# Sensorboard.net
KiCad netlist of a schematic drawn in EAGLE
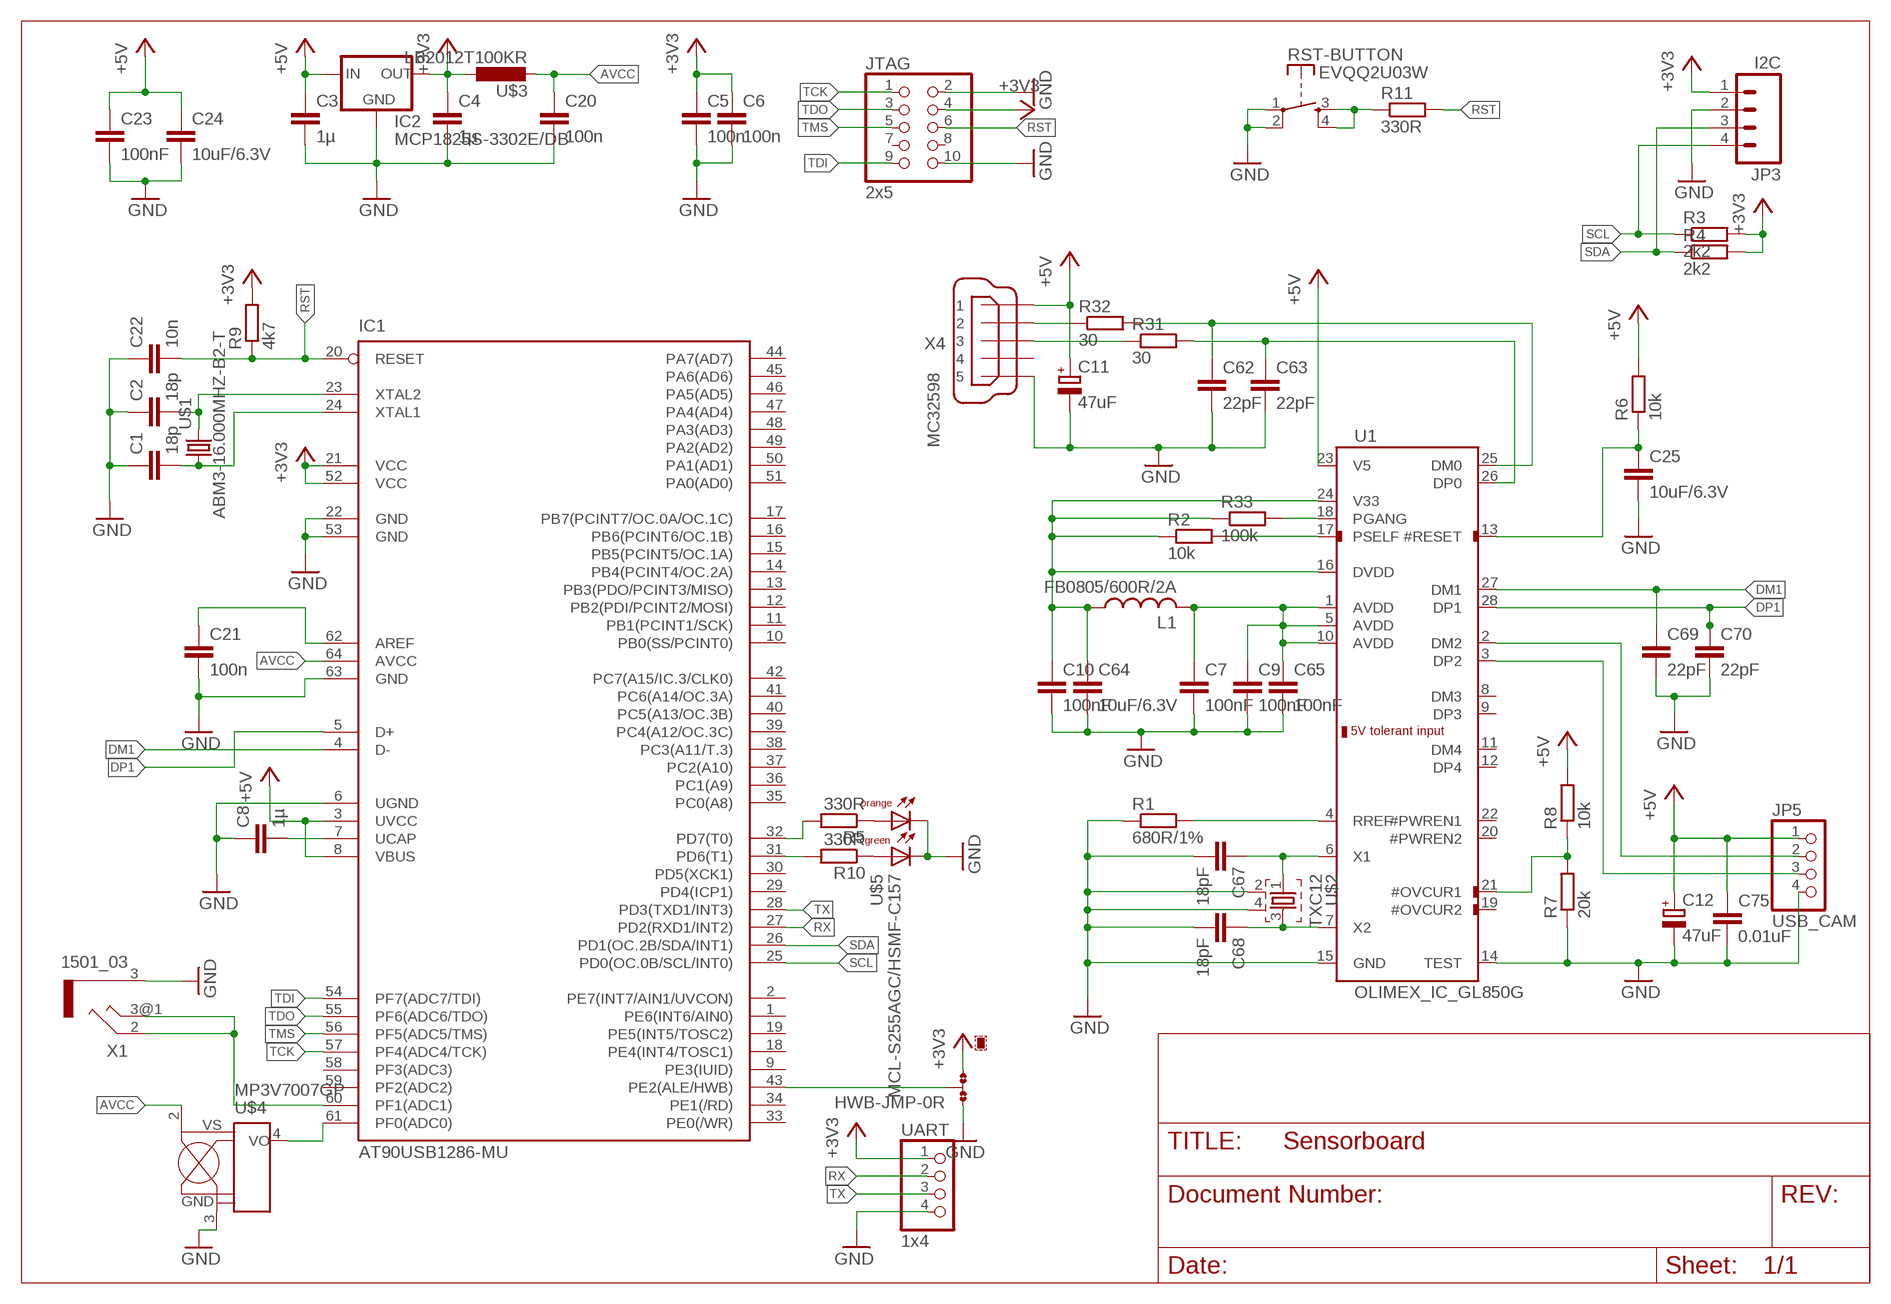
[diagram p0: schematic, sheet 1]

(export (version "E")
  (design (tool "Eeschema 10.0.6"))
  (components
    (comp (ref "C1")
      (value "18p")
      (footprint "eagle-import:C0603K")
      (libsource (lib "eagle-import") (part "C-EUC0603K"))
    )
    (comp (ref "C2")
      (value "18p")
      (footprint "eagle-import:C0603K")
      (libsource (lib "eagle-import") (part "C-EUC0603K"))
    )
    (comp (ref "C3")
      (value "1µ")
      (footprint "eagle-import:C0603K")
      (libsource (lib "eagle-import") (part "C-EUC0603K"))
    )
    (comp (ref "C4")
      (value "1µ")
      (footprint "eagle-import:C0603K")
      (libsource (lib "eagle-import") (part "C-EUC0603K"))
    )
    (comp (ref "C5")
      (value "100n")
      (footprint "eagle-import:C0603K")
      (libsource (lib "eagle-import") (part "C-EUC0603K"))
    )
    (comp (ref "C6")
      (value "100n")
      (footprint "eagle-import:C0603K")
      (libsource (lib "eagle-import") (part "C-EUC0603K"))
    )
    (comp (ref "C7")
      (value "100nF")
      (footprint "eagle-import:C0603")
      (libsource (lib "eagle-import") (part "C-EUC0603"))
    )
    (comp (ref "C8")
      (value "1µ")
      (footprint "eagle-import:C0603K")
      (libsource (lib "eagle-import") (part "C-EUC0603K"))
    )
    (comp (ref "C9")
      (value "100nF")
      (footprint "eagle-import:C0603")
      (libsource (lib "eagle-import") (part "C-EUC0603"))
    )
    (comp (ref "C10")
      (value "100nF")
      (footprint "eagle-import:C0603")
      (libsource (lib "eagle-import") (part "C-EUC0603"))
    )
    (comp (ref "C11")
      (value "47uF")
      (footprint "eagle-import:SMC_E")
      (libsource (lib "eagle-import") (part "CPOL-EUSMCE"))
    )
    (comp (ref "C12")
      (value "47uF")
      (footprint "eagle-import:SMC_E")
      (libsource (lib "eagle-import") (part "CPOL-EUSMCE"))
    )
    (comp (ref "C20")
      (value "100n")
      (footprint "eagle-import:C0603K")
      (libsource (lib "eagle-import") (part "C-EUC0603K"))
    )
    (comp (ref "C21")
      (value "100n")
      (footprint "eagle-import:C0603K")
      (libsource (lib "eagle-import") (part "C-EUC0603K"))
    )
    (comp (ref "C22")
      (value "10n")
      (footprint "eagle-import:C0603K")
      (libsource (lib "eagle-import") (part "C-EUC0603K"))
    )
    (comp (ref "C23")
      (value "100nF")
      (footprint "eagle-import:C0603")
      (libsource (lib "eagle-import") (part "C-EUC0603"))
    )
    (comp (ref "C24")
      (value "10uF/6.3V")
      (footprint "eagle-import:C0805")
      (libsource (lib "eagle-import") (part "C-EUC0805"))
    )
    (comp (ref "C25")
      (value "10uF/6.3V")
      (footprint "eagle-import:C0805")
      (libsource (lib "eagle-import") (part "C-EUC0805"))
    )
    (comp (ref "C62")
      (value "22pF")
      (footprint "eagle-import:C0603")
      (libsource (lib "eagle-import") (part "C-EUC0603"))
    )
    (comp (ref "C63")
      (value "22pF")
      (footprint "eagle-import:C0603")
      (libsource (lib "eagle-import") (part "C-EUC0603"))
    )
    (comp (ref "C64")
      (value "10uF/6.3V")
      (footprint "eagle-import:C0805")
      (libsource (lib "eagle-import") (part "C-EUC0805"))
    )
    (comp (ref "C65")
      (value "100nF")
      (footprint "eagle-import:C0603")
      (libsource (lib "eagle-import") (part "C-EUC0603"))
    )
    (comp (ref "C67")
      (value "18pF")
      (footprint "eagle-import:C0603")
      (libsource (lib "eagle-import") (part "C-EUC0603"))
    )
    (comp (ref "C68")
      (value "18pF")
      (footprint "eagle-import:C0603")
      (libsource (lib "eagle-import") (part "C-EUC0603"))
    )
    (comp (ref "C69")
      (value "22pF")
      (footprint "eagle-import:C0603")
      (libsource (lib "eagle-import") (part "C-EUC0603"))
    )
    (comp (ref "C70")
      (value "22pF")
      (footprint "eagle-import:C0603")
      (libsource (lib "eagle-import") (part "C-EUC0603"))
    )
    (comp (ref "C75")
      (value "0.01uF")
      (footprint "eagle-import:C0603")
      (libsource (lib "eagle-import") (part "C-EUC0603"))
    )
    (comp (ref "HWB-JMP")
      (value "0R-JUMPB")
      (footprint "eagle-import:B0R-JMP")
      (libsource (lib "eagle-import") (part "0R-JUMPB"))
    )
    (comp (ref "IC1")
      (value "AT90USB1286-MU")
      (footprint "eagle-import:TQFP64")
      (libsource (lib "eagle-import") (part "AT90USB1287-AU"))
    )
    (comp (ref "IC2")
      (value "MCP1825S-3302E/DB")
      (footprint "eagle-import:SOT223")
      (libsource (lib "eagle-import") (part "MCP1825-SOT223"))
    )
    (comp (ref "JP3")
      (value "I2C")
      (footprint "eagle-import:1X04")
      (libsource (lib "eagle-import") (part "M04PTH"))
    )
    (comp (ref "JP5")
      (value "USB_CAM")
      (footprint "eagle-import:1X04")
      (libsource (lib "eagle-import") (part "PINHD-1X4"))
    )
    (comp (ref "JTAG")
      (value "2x5")
      (footprint "eagle-import:2X05")
      (libsource (lib "eagle-import") (part "PINHD-2X5"))
    )
    (comp (ref "L1")
      (value "FB0805/600R/2A")
      (footprint "eagle-import:L3225P")
      (libsource (lib "eagle-import") (part "L-USL3225P"))
    )
    (comp (ref "R1")
      (value "680R/1%")
      (footprint "eagle-import:R0603")
      (libsource (lib "eagle-import") (part "R-EU_R0603"))
    )
    (comp (ref "R2")
      (value "10k")
      (footprint "eagle-import:R0603")
      (libsource (lib "eagle-import") (part "R-EU_R0603"))
    )
    (comp (ref "R3")
      (value "2k2")
      (footprint "eagle-import:R0603")
      (libsource (lib "eagle-import") (part "R-EU_R0603"))
    )
    (comp (ref "R4")
      (value "2k2")
      (footprint "eagle-import:R0603")
      (libsource (lib "eagle-import") (part "R-EU_R0603"))
    )
    (comp (ref "R5")
      (value "330R")
      (footprint "eagle-import:R0603")
      (libsource (lib "eagle-import") (part "R-EU_R0603"))
    )
    (comp (ref "R6")
      (value "10k")
      (footprint "eagle-import:R0603")
      (libsource (lib "eagle-import") (part "R-EU_R0603"))
    )
    (comp (ref "R7")
      (value "20k")
      (footprint "eagle-import:R0603")
      (libsource (lib "eagle-import") (part "R-EU_R0603"))
    )
    (comp (ref "R8")
      (value "10k")
      (footprint "eagle-import:R0603")
      (libsource (lib "eagle-import") (part "R-EU_R0603"))
    )
    (comp (ref "R9")
      (value "4k7")
      (footprint "eagle-import:R0603")
      (libsource (lib "eagle-import") (part "R-EU_R0603"))
    )
    (comp (ref "R10")
      (value "330R")
      (footprint "eagle-import:R0603")
      (libsource (lib "eagle-import") (part "R-EU_R0603"))
    )
    (comp (ref "R11")
      (value "330R")
      (footprint "eagle-import:R0603")
      (libsource (lib "eagle-import") (part "R-EU_R0603"))
    )
    (comp (ref "R31")
      (value "30")
      (footprint "eagle-import:R0603")
      (libsource (lib "eagle-import") (part "R-EU_R0603"))
    )
    (comp (ref "R32")
      (value "30")
      (footprint "eagle-import:R0603")
      (libsource (lib "eagle-import") (part "R-EU_R0603"))
    )
    (comp (ref "R33")
      (value "100k")
      (footprint "eagle-import:R0603")
      (libsource (lib "eagle-import") (part "R-EU_R0603"))
    )
    (comp (ref "RST-BUTTON")
      (value "EVQQ2U03W")
      (footprint "eagle-import:EVQQ2")
      (libsource (lib "eagle-import") (part "SWITCH-SPNO"))
    )
    (comp (ref "U$1")
      (value "ABM3-16.000MHZ-B2-T")
      (footprint "eagle-import:SMD_5X3.2MM")
      (libsource (lib "eagle-import") (part "TXC_ABM3"))
    )
    (comp (ref "U$2")
      (value "TXC12")
      (footprint "eagle-import:CTS406")
      (libsource (lib "eagle-import") (part "TXC12"))
    )
    (comp (ref "U$3")
      (value "LB2012T100KR")
      (footprint "eagle-import:L-2012")
      (libsource (lib "eagle-import") (part "L-TAIYO-YUDEN"))
    )
    (comp (ref "U$4")
      (value "MP3V7007GP")
      (footprint "eagle-import:SOP-8")
      (libsource (lib "eagle-import") (part "MP3V7007GP"))
    )
    (comp (ref "U$5")
      (value "MCL-S255AGC/HSMF-C157")
      (footprint "eagle-import:DUOLED-1210")
      (libsource (lib "eagle-import") (part "DUOLED-MULTICOMP"))
    )
    (comp (ref "U1")
      (value "OLIMEX_IC_GL850G")
      (footprint "eagle-import:OLIMEX_IC_SSOP28")
      (libsource (lib "eagle-import") (part "OLIMEX_IC_GL850G"))
    )
    (comp (ref "UART")
      (value "1x4")
      (footprint "eagle-import:1X04")
      (libsource (lib "eagle-import") (part "PINHD-1X4"))
    )
    (comp (ref "X1")
      (value "1501_03")
      (footprint "eagle-import:1503_03")
      (libsource (lib "eagle-import") (part "1501_03"))
    )
    (comp (ref "X4")
      (value "MC32598")
      (footprint "eagle-import:32005-201")
      (libsource (lib "eagle-import") (part "MINI-USB-32005-201"))
    )
  )
  (nets
    (net (code "1") (name "+3V3") (class "Default")
      (node (ref "C4") (pin "1") (pinfunction "1_1") (pintype "passive"))
      (node (ref "C5") (pin "1") (pinfunction "1_1") (pintype "passive"))
      (node (ref "C6") (pin "1") (pinfunction "1_1") (pintype "passive"))
      (node (ref "HWB-JMP") (pin "3") (pinfunction "3_3") (pintype "passive"))
      (node (ref "IC1") (pin "21") (pinfunction "VCC_21") (pintype "power_in"))
      (node (ref "IC1") (pin "52") (pinfunction "VCC_52") (pintype "power_in"))
      (node (ref "IC2") (pin "3") (pinfunction "OUT_3") (pintype "passive"))
      (node (ref "JP3") (pin "1") (pinfunction "1_1") (pintype "passive"))
      (node (ref "JTAG") (pin "4") (pinfunction "4_4") (pintype "passive"))
      (node (ref "R3") (pin "2") (pinfunction "2_2") (pintype "passive"))
      (node (ref "R4") (pin "2") (pinfunction "2_2") (pintype "passive"))
      (node (ref "R9") (pin "2") (pinfunction "2_2") (pintype "passive"))
      (node (ref "U$3") (pin "1") (pinfunction "1_1") (pintype "passive"))
      (node (ref "UART") (pin "1") (pinfunction "1_1") (pintype "passive"))
    )
    (net (code "2") (name "+5V") (class "Default")
      (node (ref "C11") (pin "+") (pinfunction "+_+") (pintype "passive"))
      (node (ref "C12") (pin "+") (pinfunction "+_+") (pintype "passive"))
      (node (ref "C23") (pin "1") (pinfunction "1_1") (pintype "passive"))
      (node (ref "C24") (pin "1") (pinfunction "1_1") (pintype "passive"))
      (node (ref "C3") (pin "1") (pinfunction "1_1") (pintype "passive"))
      (node (ref "C75") (pin "1") (pinfunction "1_1") (pintype "passive"))
      (node (ref "IC1") (pin "3") (pinfunction "UVCC_3") (pintype "power_in"))
      (node (ref "IC1") (pin "8") (pinfunction "VBUS_8") (pintype "power_in"))
      (node (ref "IC2") (pin "1") (pinfunction "IN_1") (pintype "input"))
      (node (ref "JP5") (pin "1") (pinfunction "1_1") (pintype "passive"))
      (node (ref "R6") (pin "2") (pinfunction "2_2") (pintype "passive"))
      (node (ref "R8") (pin "2") (pinfunction "2_2") (pintype "passive"))
      (node (ref "U1") (pin "23") (pinfunction "V5_23") (pintype "power_in"))
      (node (ref "X4") (pin "1") (pinfunction "1_1") (pintype "passive"))
    )
    (net (code "3") (name "AVCC") (class "Default")
      (node (ref "C20") (pin "1") (pinfunction "1_1") (pintype "passive"))
      (node (ref "IC1") (pin "64") (pinfunction "AVCC_64") (pintype "bidirectional"))
      (node (ref "U$3") (pin "2") (pinfunction "2_2") (pintype "passive"))
      (node (ref "U$4") (pin "2") (pinfunction "VS_2") (pintype "passive"))
    )
    (net (code "4") (name "DM1") (class "Default")
      (node (ref "C69") (pin "1") (pinfunction "1_1") (pintype "passive"))
      (node (ref "IC1") (pin "4") (pinfunction "D-_4") (pintype "bidirectional"))
      (node (ref "U1") (pin "27") (pinfunction "DM1_27") (pintype "bidirectional"))
    )
    (net (code "5") (name "DP1") (class "Default")
      (node (ref "C70") (pin "1") (pinfunction "1_1") (pintype "passive"))
      (node (ref "IC1") (pin "5") (pinfunction "D+_5") (pintype "bidirectional"))
      (node (ref "U1") (pin "28") (pinfunction "DP1_28") (pintype "bidirectional"))
    )
    (net (code "6") (name "GND") (class "Default")
      (node (ref "C1") (pin "1") (pinfunction "1_1") (pintype "passive"))
      (node (ref "C10") (pin "2") (pinfunction "2_2") (pintype "passive"))
      (node (ref "C11") (pin "-") (pinfunction "-_-") (pintype "passive"))
      (node (ref "C12") (pin "-") (pinfunction "-_-") (pintype "passive"))
      (node (ref "C2") (pin "1") (pinfunction "1_1") (pintype "passive"))
      (node (ref "C20") (pin "2") (pinfunction "2_2") (pintype "passive"))
      (node (ref "C21") (pin "2") (pinfunction "2_2") (pintype "passive"))
      (node (ref "C22") (pin "1") (pinfunction "1_1") (pintype "passive"))
      (node (ref "C23") (pin "2") (pinfunction "2_2") (pintype "passive"))
      (node (ref "C24") (pin "2") (pinfunction "2_2") (pintype "passive"))
      (node (ref "C25") (pin "2") (pinfunction "2_2") (pintype "passive"))
      (node (ref "C3") (pin "2") (pinfunction "2_2") (pintype "passive"))
      (node (ref "C4") (pin "2") (pinfunction "2_2") (pintype "passive"))
      (node (ref "C5") (pin "2") (pinfunction "2_2") (pintype "passive"))
      (node (ref "C6") (pin "2") (pinfunction "2_2") (pintype "passive"))
      (node (ref "C62") (pin "2") (pinfunction "2_2") (pintype "passive"))
      (node (ref "C63") (pin "2") (pinfunction "2_2") (pintype "passive"))
      (node (ref "C64") (pin "2") (pinfunction "2_2") (pintype "passive"))
      (node (ref "C65") (pin "2") (pinfunction "2_2") (pintype "passive"))
      (node (ref "C67") (pin "2") (pinfunction "2_2") (pintype "passive"))
      (node (ref "C68") (pin "2") (pinfunction "2_2") (pintype "passive"))
      (node (ref "C69") (pin "2") (pinfunction "2_2") (pintype "passive"))
      (node (ref "C7") (pin "2") (pinfunction "2_2") (pintype "passive"))
      (node (ref "C70") (pin "2") (pinfunction "2_2") (pintype "passive"))
      (node (ref "C75") (pin "2") (pinfunction "2_2") (pintype "passive"))
      (node (ref "C8") (pin "1") (pinfunction "1_1") (pintype "passive"))
      (node (ref "C9") (pin "2") (pinfunction "2_2") (pintype "passive"))
      (node (ref "HWB-JMP") (pin "1") (pinfunction "1_1") (pintype "passive"))
      (node (ref "IC1") (pin "22") (pinfunction "GND_22") (pintype "power_in"))
      (node (ref "IC1") (pin "53") (pinfunction "GND_53") (pintype "power_in"))
      (node (ref "IC1") (pin "6") (pinfunction "UGND_6") (pintype "power_in"))
      (node (ref "IC1") (pin "63") (pinfunction "GND_63") (pintype "power_in"))
      (node (ref "IC2") (pin "2") (pinfunction "GND_2") (pintype "input"))
      (node (ref "IC2") (pin "4") (pinfunction "GND_4") (pintype "input"))
      (node (ref "JP3") (pin "2") (pinfunction "2_2") (pintype "passive"))
      (node (ref "JP5") (pin "4") (pinfunction "4_4") (pintype "passive"))
      (node (ref "JTAG") (pin "10") (pinfunction "10_10") (pintype "passive"))
      (node (ref "JTAG") (pin "2") (pinfunction "2_2") (pintype "passive"))
      (node (ref "R1") (pin "1") (pinfunction "1_1") (pintype "passive"))
      (node (ref "R7") (pin "1") (pinfunction "1_1") (pintype "passive"))
      (node (ref "RST-BUTTON") (pin "1") (pinfunction "P_1") (pintype "passive"))
      (node (ref "RST-BUTTON") (pin "2") (pinfunction "P_2") (pintype "passive"))
      (node (ref "U$2") (pin "2") (pinfunction "2_2") (pintype "passive"))
      (node (ref "U$2") (pin "4") (pinfunction "4_4") (pintype "passive"))
      (node (ref "U$4") (pin "3") (pinfunction "GND_3") (pintype "passive"))
      (node (ref "U$5") (pin "1") (pinfunction "C_1") (pintype "passive"))
      (node (ref "U$5") (pin "2") (pinfunction "C_2") (pintype "passive"))
      (node (ref "U1") (pin "14") (pinfunction "TEST_14") (pintype "input"))
      (node (ref "U1") (pin "15") (pinfunction "GND_15") (pintype "power_in"))
      (node (ref "UART") (pin "4") (pinfunction "4_4") (pintype "passive"))
      (node (ref "X1") (pin "3") (pinfunction "1_3") (pintype "passive"))
      (node (ref "X4") (pin "5") (pinfunction "5_5") (pintype "passive"))
    )
    (net (code "7") (name "Net-(C65-Pad1)") (class "Default")
      (node (ref "C65") (pin "1") (pinfunction "1_1") (pintype "passive"))
      (node (ref "C7") (pin "1") (pinfunction "1_1") (pintype "passive"))
      (node (ref "C9") (pin "1") (pinfunction "1_1") (pintype "passive"))
      (node (ref "L1") (pin "2") (pinfunction "2_2") (pintype "passive"))
      (node (ref "U1") (pin "1") (pinfunction "AVDD_1") (pintype "power_in"))
      (node (ref "U1") (pin "10") (pinfunction "AVDD_10") (pintype "power_in"))
      (node (ref "U1") (pin "5") (pinfunction "AVDD_5") (pintype "power_in"))
    )
    (net (code "8") (name "Net-(IC1-AREF)") (class "Default")
      (node (ref "C21") (pin "1") (pinfunction "1_1") (pintype "passive"))
      (node (ref "IC1") (pin "62") (pinfunction "AREF_62") (pintype "bidirectional"))
    )
    (net (code "9") (name "Net-(IC1-PD6(T1))") (class "Default")
      (node (ref "IC1") (pin "31") (pinfunction "PD6(T1)_31") (pintype "bidirectional"))
      (node (ref "R10") (pin "2") (pinfunction "2_2") (pintype "passive"))
    )
    (net (code "10") (name "Net-(IC1-PD7(T0))") (class "Default")
      (node (ref "IC1") (pin "32") (pinfunction "PD7(T0)_32") (pintype "bidirectional"))
      (node (ref "R5") (pin "2") (pinfunction "2_2") (pintype "passive"))
    )
    (net (code "11") (name "Net-(IC1-PE2(ALE{slash}HWB))") (class "Default")
      (node (ref "HWB-JMP") (pin "2") (pinfunction "2_2") (pintype "passive"))
      (node (ref "IC1") (pin "43") (pinfunction "PE2(ALE/HWB)_43") (pintype "bidirectional"))
    )
    (net (code "12") (name "Net-(IC1-PF0(ADC0))") (class "Default")
      (node (ref "IC1") (pin "61") (pinfunction "PF0(ADC0)_61") (pintype "bidirectional"))
      (node (ref "U$4") (pin "4") (pinfunction "OUT_4") (pintype "passive"))
    )
    (net (code "13") (name "Net-(IC1-PF1(ADC1))") (class "Default")
      (node (ref "IC1") (pin "60") (pinfunction "PF1(ADC1)_60") (pintype "bidirectional"))
      (node (ref "X1") (pin "2") (pinfunction "2_2") (pintype "passive"))
      (node (ref "X1") (pin "3@1") (pinfunction "3_3@1") (pintype "passive"))
    )
    (net (code "14") (name "Net-(IC1-UCAP)") (class "Default")
      (node (ref "C8") (pin "2") (pinfunction "2_2") (pintype "passive"))
      (node (ref "IC1") (pin "7") (pinfunction "UCAP_7") (pintype "power_in"))
    )
    (net (code "15") (name "Net-(IC1-XTAL1)") (class "Default")
      (node (ref "C1") (pin "2") (pinfunction "2_2") (pintype "passive"))
      (node (ref "IC1") (pin "24") (pinfunction "XTAL1_24") (pintype "bidirectional"))
      (node (ref "U$1") (pin "P$1") (pinfunction "1_P$1") (pintype "passive"))
    )
    (net (code "16") (name "Net-(IC1-XTAL2)") (class "Default")
      (node (ref "C2") (pin "2") (pinfunction "2_2") (pintype "passive"))
      (node (ref "IC1") (pin "23") (pinfunction "XTAL2_23") (pintype "bidirectional"))
      (node (ref "U$1") (pin "P$2") (pinfunction "2_P$2") (pintype "passive"))
    )
    (net (code "17") (name "Net-(R11-Pad1)") (class "Default")
      (node (ref "R11") (pin "1") (pinfunction "1_1") (pintype "passive"))
      (node (ref "RST-BUTTON") (pin "3") (pinfunction "S_3") (pintype "passive"))
      (node (ref "RST-BUTTON") (pin "4") (pinfunction "S_4") (pintype "passive"))
    )
    (net (code "18") (name "Net-(R31-Pad1)") (class "Default")
      (node (ref "R31") (pin "1") (pinfunction "1_1") (pintype "passive"))
      (node (ref "X4") (pin "3") (pinfunction "3_3") (pintype "passive"))
    )
    (net (code "19") (name "Net-(R32-Pad1)") (class "Default")
      (node (ref "R32") (pin "1") (pinfunction "1_1") (pintype "passive"))
      (node (ref "X4") (pin "2") (pinfunction "2_2") (pintype "passive"))
    )
    (net (code "20") (name "Net-(U$5-AG)") (class "Default")
      (node (ref "R10") (pin "1") (pinfunction "1_1") (pintype "passive"))
      (node (ref "U$5") (pin "3") (pinfunction "AG_3") (pintype "passive"))
    )
    (net (code "21") (name "Net-(U$5-AO)") (class "Default")
      (node (ref "R5") (pin "1") (pinfunction "1_1") (pintype "passive"))
      (node (ref "U$5") (pin "4") (pinfunction "AO_4") (pintype "passive"))
    )
    (net (code "22") (name "Net-(U1-#OVCUR1)") (class "Default")
      (node (ref "R7") (pin "2") (pinfunction "2_2") (pintype "passive"))
      (node (ref "R8") (pin "1") (pinfunction "1_1") (pintype "passive"))
      (node (ref "U1") (pin "21") (pinfunction "#OVCUR1_21") (pintype "bidirectional"))
    )
    (net (code "23") (name "Net-(U1-#RESET)") (class "Default")
      (node (ref "C25") (pin "1") (pinfunction "1_1") (pintype "passive"))
      (node (ref "R6") (pin "1") (pinfunction "1_1") (pintype "passive"))
      (node (ref "U1") (pin "13") (pinfunction "#RESET_13") (pintype "bidirectional"))
    )
    (net (code "24") (name "Net-(U1-DM0)") (class "Default")
      (node (ref "C62") (pin "1") (pinfunction "1_1") (pintype "passive"))
      (node (ref "R32") (pin "2") (pinfunction "2_2") (pintype "passive"))
      (node (ref "U1") (pin "25") (pinfunction "DM0_25") (pintype "bidirectional"))
    )
    (net (code "25") (name "Net-(U1-DM2)") (class "Default")
      (node (ref "JP5") (pin "2") (pinfunction "2_2") (pintype "passive"))
      (node (ref "U1") (pin "2") (pinfunction "DM2_2") (pintype "bidirectional"))
    )
    (net (code "26") (name "Net-(U1-DP0)") (class "Default")
      (node (ref "C63") (pin "1") (pinfunction "1_1") (pintype "passive"))
      (node (ref "R31") (pin "2") (pinfunction "2_2") (pintype "passive"))
      (node (ref "U1") (pin "26") (pinfunction "DP0_26") (pintype "bidirectional"))
    )
    (net (code "27") (name "Net-(U1-DP2)") (class "Default")
      (node (ref "JP5") (pin "3") (pinfunction "3_3") (pintype "passive"))
      (node (ref "U1") (pin "3") (pinfunction "DP2_3") (pintype "bidirectional"))
    )
    (net (code "28") (name "Net-(U1-DVDD)") (class "Default")
      (node (ref "C10") (pin "1") (pinfunction "1_1") (pintype "passive"))
      (node (ref "C64") (pin "1") (pinfunction "1_1") (pintype "passive"))
      (node (ref "L1") (pin "1") (pinfunction "1_1") (pintype "passive"))
      (node (ref "R2") (pin "1") (pinfunction "1_1") (pintype "passive"))
      (node (ref "R33") (pin "1") (pinfunction "1_1") (pintype "passive"))
      (node (ref "U1") (pin "16") (pinfunction "DVDD_16") (pintype "power_in"))
      (node (ref "U1") (pin "24") (pinfunction "V33_24") (pintype "power_in"))
    )
    (net (code "29") (name "Net-(U1-PGANG)") (class "Default")
      (node (ref "R33") (pin "2") (pinfunction "2_2") (pintype "passive"))
      (node (ref "U1") (pin "18") (pinfunction "PGANG_18") (pintype "bidirectional"))
    )
    (net (code "30") (name "Net-(U1-PSELF)") (class "Default")
      (node (ref "R2") (pin "2") (pinfunction "2_2") (pintype "passive"))
      (node (ref "U1") (pin "17") (pinfunction "PSELF_17") (pintype "bidirectional"))
    )
    (net (code "31") (name "Net-(U1-RREF)") (class "Default")
      (node (ref "R1") (pin "2") (pinfunction "2_2") (pintype "passive"))
      (node (ref "U1") (pin "4") (pinfunction "RREF_4") (pintype "bidirectional"))
    )
    (net (code "32") (name "Net-(U1-X1)") (class "Default")
      (node (ref "C67") (pin "1") (pinfunction "1_1") (pintype "passive"))
      (node (ref "U$2") (pin "1") (pinfunction "1_1") (pintype "passive"))
      (node (ref "U1") (pin "6") (pinfunction "X1_6") (pintype "input"))
    )
    (net (code "33") (name "Net-(U1-X2)") (class "Default")
      (node (ref "C68") (pin "1") (pinfunction "1_1") (pintype "passive"))
      (node (ref "U$2") (pin "3") (pinfunction "3_3") (pintype "passive"))
      (node (ref "U1") (pin "7") (pinfunction "X2_7") (pintype "output"))
    )
    (net (code "34") (name "RST") (class "Default")
      (node (ref "C22") (pin "2") (pinfunction "2_2") (pintype "passive"))
      (node (ref "IC1") (pin "20") (pinfunction "RESET_20") (pintype "input"))
      (node (ref "JTAG") (pin "6") (pinfunction "6_6") (pintype "passive"))
      (node (ref "R11") (pin "2") (pinfunction "2_2") (pintype "passive"))
      (node (ref "R9") (pin "1") (pinfunction "1_1") (pintype "passive"))
    )
    (net (code "35") (name "RX") (class "Default")
      (node (ref "IC1") (pin "27") (pinfunction "PD2(RXD1/INT2)_27") (pintype "bidirectional"))
      (node (ref "UART") (pin "2") (pinfunction "2_2") (pintype "passive"))
    )
    (net (code "36") (name "SCL") (class "Default")
      (node (ref "IC1") (pin "25") (pinfunction "PD0(OC.0B/SCL/INT0)_25") (pintype "bidirectional"))
      (node (ref "JP3") (pin "4") (pinfunction "4_4") (pintype "passive"))
      (node (ref "R3") (pin "1") (pinfunction "1_1") (pintype "passive"))
    )
    (net (code "37") (name "SDA") (class "Default")
      (node (ref "IC1") (pin "26") (pinfunction "PD1(OC.2B/SDA/INT1)_26") (pintype "bidirectional"))
      (node (ref "JP3") (pin "3") (pinfunction "3_3") (pintype "passive"))
      (node (ref "R4") (pin "1") (pinfunction "1_1") (pintype "passive"))
    )
    (net (code "38") (name "TCK") (class "Default")
      (node (ref "IC1") (pin "57") (pinfunction "PF4(ADC4/TCK)_57") (pintype "bidirectional"))
      (node (ref "JTAG") (pin "1") (pinfunction "1_1") (pintype "passive"))
    )
    (net (code "39") (name "TDI") (class "Default")
      (node (ref "IC1") (pin "54") (pinfunction "PF7(ADC7/TDI)_54") (pintype "bidirectional"))
      (node (ref "JTAG") (pin "9") (pinfunction "9_9") (pintype "passive"))
    )
    (net (code "40") (name "TDO") (class "Default")
      (node (ref "IC1") (pin "55") (pinfunction "PF6(ADC6/TDO)_55") (pintype "bidirectional"))
      (node (ref "JTAG") (pin "3") (pinfunction "3_3") (pintype "passive"))
    )
    (net (code "41") (name "TMS") (class "Default")
      (node (ref "IC1") (pin "56") (pinfunction "PF5(ADC5/TMS)_56") (pintype "bidirectional"))
      (node (ref "JTAG") (pin "5") (pinfunction "5_5") (pintype "passive"))
    )
    (net (code "42") (name "TX") (class "Default")
      (node (ref "IC1") (pin "28") (pinfunction "PD3(TXD1/INT3)_28") (pintype "bidirectional"))
      (node (ref "UART") (pin "3") (pinfunction "3_3") (pintype "passive"))
    )
    (net (code "43") (name "unconnected-(IC1-PA0(AD0)-Pad51)") (class "Default")
      (node (ref "IC1") (pin "51") (pinfunction "PA0(AD0)_51") (pintype "bidirectional"))
    )
    (net (code "44") (name "unconnected-(IC1-PA1(AD1)-Pad50)") (class "Default")
      (node (ref "IC1") (pin "50") (pinfunction "PA1(AD1)_50") (pintype "bidirectional"))
    )
    (net (code "45") (name "unconnected-(IC1-PA2(AD2)-Pad49)") (class "Default")
      (node (ref "IC1") (pin "49") (pinfunction "PA2(AD2)_49") (pintype "bidirectional"))
    )
    (net (code "46") (name "unconnected-(IC1-PA3(AD3)-Pad48)") (class "Default")
      (node (ref "IC1") (pin "48") (pinfunction "PA3(AD3)_48") (pintype "bidirectional"))
    )
    (net (code "47") (name "unconnected-(IC1-PA4(AD4)-Pad47)") (class "Default")
      (node (ref "IC1") (pin "47") (pinfunction "PA4(AD4)_47") (pintype "bidirectional"))
    )
    (net (code "48") (name "unconnected-(IC1-PA5(AD5)-Pad46)") (class "Default")
      (node (ref "IC1") (pin "46") (pinfunction "PA5(AD5)_46") (pintype "bidirectional"))
    )
    (net (code "49") (name "unconnected-(IC1-PA6(AD6)-Pad45)") (class "Default")
      (node (ref "IC1") (pin "45") (pinfunction "PA6(AD6)_45") (pintype "bidirectional"))
    )
    (net (code "50") (name "unconnected-(IC1-PA7(AD7)-Pad44)") (class "Default")
      (node (ref "IC1") (pin "44") (pinfunction "PA7(AD7)_44") (pintype "bidirectional"))
    )
    (net (code "51") (name "unconnected-(IC1-PB0(SS{slash}PCINT0)-Pad10)") (class "Default")
      (node (ref "IC1") (pin "10") (pinfunction "PB0(SS/PCINT0)_10") (pintype "bidirectional"))
    )
    (net (code "52") (name "unconnected-(IC1-PB1(PCINT1{slash}SCK)-Pad11)") (class "Default")
      (node (ref "IC1") (pin "11") (pinfunction "PB1(PCINT1/SCK)_11") (pintype "bidirectional"))
    )
    (net (code "53") (name "unconnected-(IC1-PB2(PDI{slash}PCINT2{slash}MOSI)-Pad12)") (class "Default")
      (node (ref "IC1") (pin "12") (pinfunction "PB2(PDI/PCINT2/MOSI)_12") (pintype "bidirectional"))
    )
    (net (code "54") (name "unconnected-(IC1-PB3(PDO{slash}PCINT3{slash}MISO)-Pad13)") (class "Default")
      (node (ref "IC1") (pin "13") (pinfunction "PB3(PDO/PCINT3/MISO)_13") (pintype "bidirectional"))
    )
    (net (code "55") (name "unconnected-(IC1-PB4(PCINT4{slash}OC.2A)-Pad14)") (class "Default")
      (node (ref "IC1") (pin "14") (pinfunction "PB4(PCINT4/OC.2A)_14") (pintype "bidirectional"))
    )
    (net (code "56") (name "unconnected-(IC1-PB5(PCINT5{slash}OC.1A)-Pad15)") (class "Default")
      (node (ref "IC1") (pin "15") (pinfunction "PB5(PCINT5/OC.1A)_15") (pintype "bidirectional"))
    )
    (net (code "57") (name "unconnected-(IC1-PB6(PCINT6{slash}OC.1B)-Pad16)") (class "Default")
      (node (ref "IC1") (pin "16") (pinfunction "PB6(PCINT6/OC.1B)_16") (pintype "bidirectional"))
    )
    (net (code "58") (name "unconnected-(IC1-PB7(PCINT7{slash}OC.0A{slash}OC.1C)-Pad17)") (class "Default")
      (node (ref "IC1") (pin "17") (pinfunction "PB7(PCINT7/OC.0A/OC.1C)_17") (pintype "bidirectional"))
    )
    (net (code "59") (name "unconnected-(IC1-PC0(A8)-Pad35)") (class "Default")
      (node (ref "IC1") (pin "35") (pinfunction "PC0(A8)_35") (pintype "bidirectional"))
    )
    (net (code "60") (name "unconnected-(IC1-PC1(A9)-Pad36)") (class "Default")
      (node (ref "IC1") (pin "36") (pinfunction "PC1(A9)_36") (pintype "bidirectional"))
    )
    (net (code "61") (name "unconnected-(IC1-PC2(A10)-Pad37)") (class "Default")
      (node (ref "IC1") (pin "37") (pinfunction "PC2(A10)_37") (pintype "bidirectional"))
    )
    (net (code "62") (name "unconnected-(IC1-PC3(A11{slash}T.3)-Pad38)") (class "Default")
      (node (ref "IC1") (pin "38") (pinfunction "PC3(A11/T.3)_38") (pintype "bidirectional"))
    )
    (net (code "63") (name "unconnected-(IC1-PC4(A12{slash}OC.3C)-Pad39)") (class "Default")
      (node (ref "IC1") (pin "39") (pinfunction "PC4(A12/OC.3C)_39") (pintype "bidirectional"))
    )
    (net (code "64") (name "unconnected-(IC1-PC5(A13{slash}OC.3B)-Pad40)") (class "Default")
      (node (ref "IC1") (pin "40") (pinfunction "PC5(A13/OC.3B)_40") (pintype "bidirectional"))
    )
    (net (code "65") (name "unconnected-(IC1-PC6(A14{slash}OC.3A)-Pad41)") (class "Default")
      (node (ref "IC1") (pin "41") (pinfunction "PC6(A14/OC.3A)_41") (pintype "bidirectional"))
    )
    (net (code "66") (name "unconnected-(IC1-PC7(A15{slash}IC.3{slash}CLK0)-Pad42)") (class "Default")
      (node (ref "IC1") (pin "42") (pinfunction "PC7(A15/IC.3/CLK0)_42") (pintype "bidirectional"))
    )
    (net (code "67") (name "unconnected-(IC1-PD4(ICP1)-Pad29)") (class "Default")
      (node (ref "IC1") (pin "29") (pinfunction "PD4(ICP1)_29") (pintype "bidirectional"))
    )
    (net (code "68") (name "unconnected-(IC1-PD5(XCK1)-Pad30)") (class "Default")
      (node (ref "IC1") (pin "30") (pinfunction "PD5(XCK1)_30") (pintype "bidirectional"))
    )
    (net (code "69") (name "unconnected-(IC1-PE0({slash}WR)-Pad33)") (class "Default")
      (node (ref "IC1") (pin "33") (pinfunction "PE0(/WR)_33") (pintype "bidirectional"))
    )
    (net (code "70") (name "unconnected-(IC1-PE1({slash}RD)-Pad34)") (class "Default")
      (node (ref "IC1") (pin "34") (pinfunction "PE1(/RD)_34") (pintype "bidirectional"))
    )
    (net (code "71") (name "unconnected-(IC1-PE3(IUID)-Pad9)") (class "Default")
      (node (ref "IC1") (pin "9") (pinfunction "PE3(IUID)_9") (pintype "bidirectional"))
    )
    (net (code "72") (name "unconnected-(IC1-PE4(INT4{slash}TOSC1)-Pad18)") (class "Default")
      (node (ref "IC1") (pin "18") (pinfunction "PE4(INT4/TOSC1)_18") (pintype "bidirectional"))
    )
    (net (code "73") (name "unconnected-(IC1-PE5(INT5{slash}TOSC2)-Pad19)") (class "Default")
      (node (ref "IC1") (pin "19") (pinfunction "PE5(INT5/TOSC2)_19") (pintype "bidirectional"))
    )
    (net (code "74") (name "unconnected-(IC1-PE6(INT6{slash}AIN0)-Pad1)") (class "Default")
      (node (ref "IC1") (pin "1") (pinfunction "PE6(INT6/AIN0)_1") (pintype "bidirectional"))
    )
    (net (code "75") (name "unconnected-(IC1-PE7(INT7{slash}AIN1{slash}UVCON)-Pad2)") (class "Default")
      (node (ref "IC1") (pin "2") (pinfunction "PE7(INT7/AIN1/UVCON)_2") (pintype "bidirectional"))
    )
    (net (code "76") (name "unconnected-(IC1-PF2(ADC2)-Pad59)") (class "Default")
      (node (ref "IC1") (pin "59") (pinfunction "PF2(ADC2)_59") (pintype "bidirectional"))
    )
    (net (code "77") (name "unconnected-(IC1-PF3(ADC3)-Pad58)") (class "Default")
      (node (ref "IC1") (pin "58") (pinfunction "PF3(ADC3)_58") (pintype "bidirectional"))
    )
    (net (code "78") (name "unconnected-(JTAG-Pad7)") (class "Default")
      (node (ref "JTAG") (pin "7") (pinfunction "7_7") (pintype "passive"))
    )
    (net (code "79") (name "unconnected-(JTAG-Pad8)") (class "Default")
      (node (ref "JTAG") (pin "8") (pinfunction "8_8") (pintype "passive"))
    )
    (net (code "80") (name "unconnected-(U1-#OVCUR2-Pad19)") (class "Default")
      (node (ref "U1") (pin "19") (pinfunction "#OVCUR2_19") (pintype "bidirectional"))
    )
    (net (code "81") (name "unconnected-(U1-#PWREN1-Pad22)") (class "Default")
      (node (ref "U1") (pin "22") (pinfunction "#PWREN1_22") (pintype "output"))
    )
    (net (code "82") (name "unconnected-(U1-#PWREN2-Pad20)") (class "Default")
      (node (ref "U1") (pin "20") (pinfunction "#PWREN2_20") (pintype "output"))
    )
    (net (code "83") (name "unconnected-(U1-DM3-Pad8)") (class "Default")
      (node (ref "U1") (pin "8") (pinfunction "DM3_8") (pintype "bidirectional"))
    )
    (net (code "84") (name "unconnected-(U1-DM4-Pad11)") (class "Default")
      (node (ref "U1") (pin "11") (pinfunction "DM4_11") (pintype "bidirectional"))
    )
    (net (code "85") (name "unconnected-(U1-DP3-Pad9)") (class "Default")
      (node (ref "U1") (pin "9") (pinfunction "DP3_9") (pintype "bidirectional"))
    )
    (net (code "86") (name "unconnected-(U1-DP4-Pad12)") (class "Default")
      (node (ref "U1") (pin "12") (pinfunction "DP4_12") (pintype "bidirectional"))
    )
    (net (code "87") (name "unconnected-(X4-Pad4)") (class "Default")
      (node (ref "X4") (pin "4") (pinfunction "4_4") (pintype "passive"))
    )
  )
)
